# Main_Circuit_Schematic.net
KiCad netlist of a schematic drawn in Altium Designer
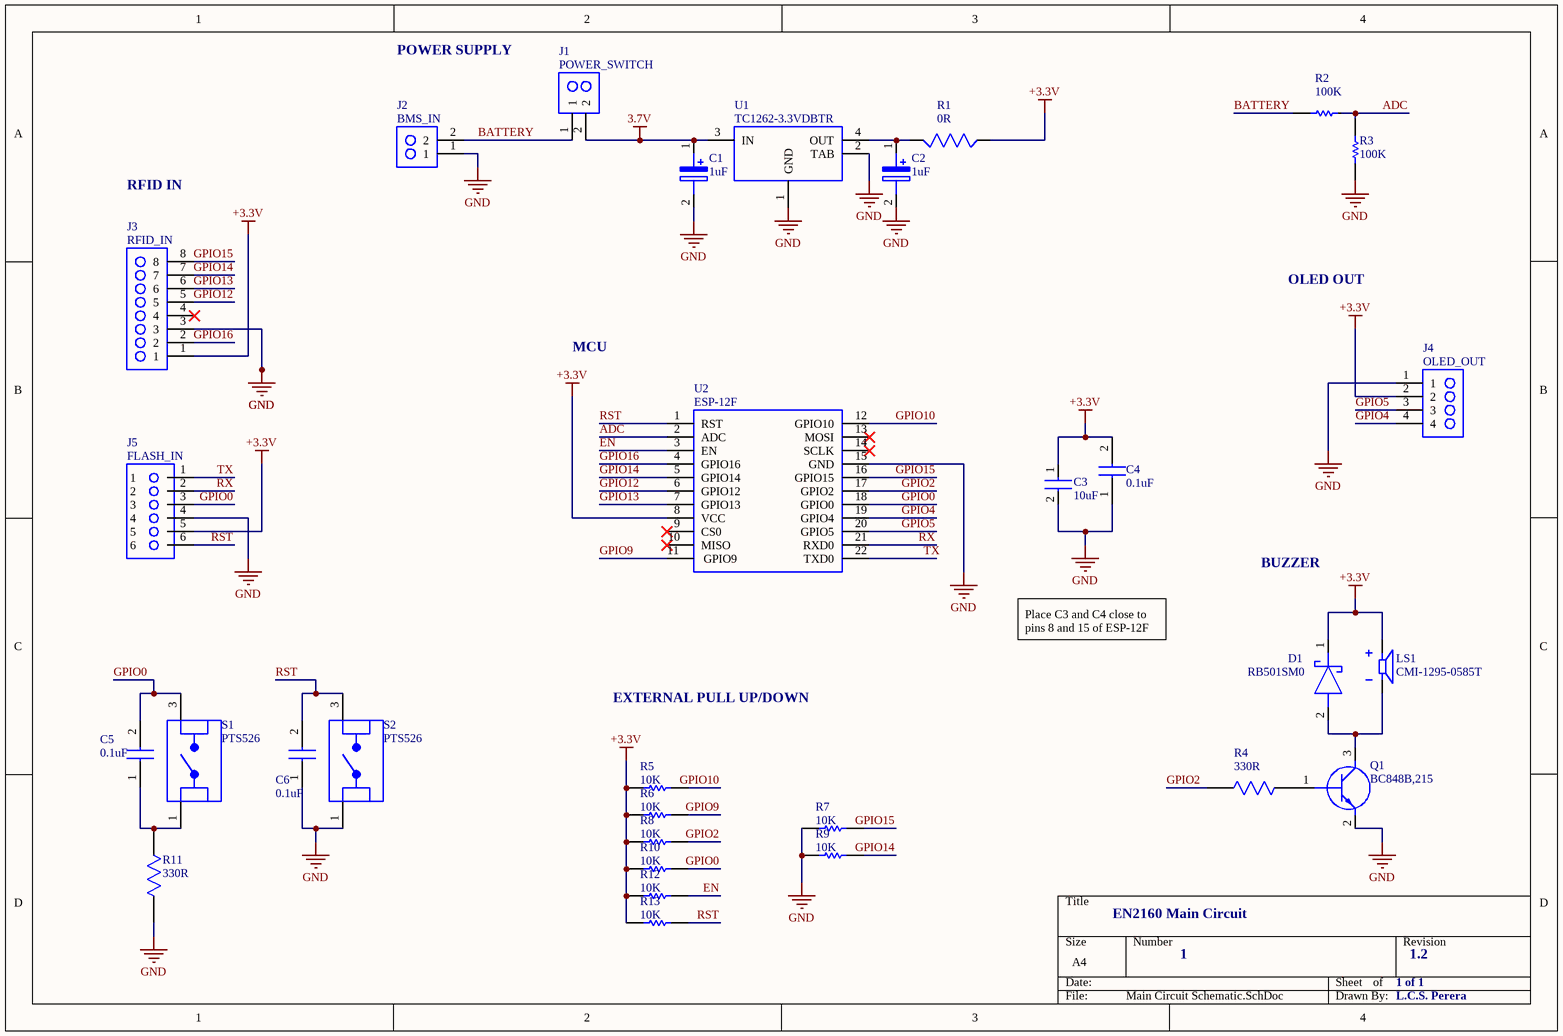
[diagram p0: Main Circuit Schematic.SchDoc]

(export (version "E")
  (design (tool "Eeschema 10.0.6"))
  (components
    (comp (ref "C1")
      (value "1uF")
      (footprint "1U")
      (description "Capacitor Polarised")
      (fields
        (field (name "MANUFACTURER_PART_NUMBER") "TAJA105K016RNJ")
        (field (name "MOUSER PART NUMBER") "581-TAJA105K016")
      )
      (libsource (lib "Schlib1") (part "TAJA105K016RNJ"))
    )
    (comp (ref "C2")
      (value "1uF")
      (footprint "1U")
      (description "Capacitor Polarised")
      (fields
        (field (name "MANUFACTURER_PART_NUMBER") "TAJA105K016RNJ")
        (field (name "MOUSER PART NUMBER") "581-TAJA105K016")
      )
      (libsource (lib "Schlib1") (part "TAJA105K016RNJ"))
    )
    (comp (ref "C3")
      (value "10uF")
      (footprint "10ucer")
      (description "10ÂµF Â±10% 10V Ceramic Capacitor X5R 0805 (2012 Metric)")
      (fields
        (field (name "MF") "Samsung Electro-Mechanics")
        (field (name "DIGI-KEY_PART_NUMBER") "1276-6456-1-ND")
      )
      (libsource (lib "Schlib1") (part "10uF"))
    )
    (comp (ref "C4")
      (value "0.1uF")
      (footprint "100n")
      (description "Capacitor")
      (fields
        (field (name "MANUFACTURER_PART_NUMBER") "C0603C104K1RACTU")
        (field (name "MOUSER PART NUMBER") "80-C0603C104K1RACTU")
      )
      (libsource (lib "Schlib1") (part "0.1uF"))
    )
    (comp (ref "C5")
      (value "0.1uF")
      (footprint "100n")
      (description "Capacitor")
      (fields
        (field (name "MANUFACTURER_PART_NUMBER") "C0603C104K1RACTU")
        (field (name "MOUSER PART NUMBER") "80-C0603C104K1RACTU")
      )
      (libsource (lib "Schlib1") (part "0.1uF"))
    )
    (comp (ref "C6")
      (value "0.1uF")
      (footprint "100n")
      (description "Capacitor")
      (fields
        (field (name "MANUFACTURER_PART_NUMBER") "C0603C104K1RACTU")
        (field (name "MOUSER PART NUMBER") "80-C0603C104K1RACTU")
      )
      (libsource (lib "Schlib1") (part "0.1uF"))
    )
    (comp (ref "D1")
      (value "RB501SM0")
      (footprint "Shottkey")
      (description "Schottky Diode")
      (fields (field (name "MANUFACTURER_PART_NUMBER") "RB501SM-30"))
      (libsource (lib "Schlib1") (part "RB501SM-30"))
    )
    (comp (ref "J1")
      (value "POWER_SWITCH")
      (footprint "2jst")
      (description "Connector")
      (fields (field (name "MANUFACTURER_PART_NUMBER") "B2B-XH-A(LF)(SN)"))
      (libsource (lib "Schlib1") (part "B2B-XHALFSN_"))
    )
    (comp (ref "J2")
      (value "BMS_IN")
      (footprint "2jst")
      (description "Connector")
      (fields (field (name "MANUFACTURER_PART_NUMBER") "B2B-XH-A(LF)(SN)"))
      (libsource (lib "") (part "B2B-XHALFSN__1"))
    )
    (comp (ref "J3")
      (value "RFID_IN")
      (footprint "8x1")
      (description "Connector")
      (fields
        (field (name "MANUFACTURER_PART_NUMBER") "61300811121")
        (field (name "MOUSER PART NUMBER") "710-61300811121")
      )
      (libsource (lib "Schlib1") (part "61300811121"))
    )
    (comp (ref "J4")
      (value "OLED_OUT")
      (footprint "4x1")
      (description "GROVE 2MM 4PIN VERT CONN 10PCS")
      (fields (field (name "MP") "110990030") (field (name "MF") "Seeed Technology"))
      (libsource (lib "Schlib1") (part "4x1"))
    )
    (comp (ref "J5")
      (value "FLASH_IN")
      (footprint "6x1")
      (description "6 Position Header Connector 0.100 (2.54mm) Through Hole Tin")
      (fields (field (name "MF") "Sullins Connector") (field (name "MP") "PPTC061LFBN-RC"))
      (libsource (lib "Schlib1") (part "PPTC061LFBN-RC"))
    )
    (comp (ref "LS1")
      (value "CMI-1295-0585T")
      (footprint "BUZZER")
      (description "12 mm, 5 Vdc, 85 dB, Through Hole, Driving Circuit, Magnetic Audio Indicator Buzzer")
      (fields (field (name "MF") "CUI Devices"))
      (libsource (lib "Schlib1") (part "CMI-1295-0585T"))
    )
    (comp (ref "Q1")
      (value "BC848B,215")
      (footprint "BC8488")
      (description "Transistor BJT NPN")
      (fields (field (name "MOUSER PART NUMBER") "771-BC848B215"))
      (libsource (lib "Schlib1") (part "BC848B,215"))
    )
    (comp (ref "R1")
      (value "0R")
      (footprint "0ohm")
      (description "0 Ohms Jumper 0.125W, 1/8W Chip Resistor 0805 (2012 Metric) Moisture Resistant Thick Film")
      (fields (field (name "MF") "Yageo") (field (name "MP") "RC0805JR-070RL"))
      (libsource (lib "Schlib1") (part "RC0805JR-070RL"))
    )
    (comp (ref "R2")
      (value "100K")
      (footprint "100k")
      (description "Resistor")
      (fields
        (field (name "MANUFACTURER_PART_NUMBER") "CR0805-FX-1002ELF")
        (field (name "MOUSER PART NUMBER") "652-CR0805FX-1002ELF")
      )
      (libsource (lib "Schlib1") (part "100k"))
    )
    (comp (ref "R3")
      (value "100K")
      (footprint "100k")
      (description "Resistor")
      (fields
        (field (name "MANUFACTURER_PART_NUMBER") "CR0805-FX-1002ELF")
        (field (name "MOUSER PART NUMBER") "652-CR0805FX-1002ELF")
      )
      (libsource (lib "Schlib1") (part "100k"))
    )
    (comp (ref "R4")
      (value "330R")
      (footprint "330r")
      (description "Resistor")
      (fields
        (field (name "MANUFACTURER_PART_NUMBER") "CR0805-FX-3300ELF")
        (field (name "MOUSER PART NUMBER") "652-CR0805FX-3300ELF")
      )
      (libsource (lib "Schlib1") (part "CR0805-FX-3300ELF"))
    )
    (comp (ref "R5")
      (value "10K")
      (footprint "10k")
      (description "Resistor")
      (fields
        (field (name "MANUFACTURER_PART_NUMBER") "CR0805-FX-1002ELF")
        (field (name "MOUSER PART NUMBER") "652-CR0805FX-1002ELF")
      )
      (libsource (lib "Schlib1") (part "10k"))
    )
    (comp (ref "R6")
      (value "10K")
      (footprint "10k")
      (description "Resistor")
      (fields
        (field (name "MANUFACTURER_PART_NUMBER") "CR0805-FX-1002ELF")
        (field (name "MOUSER PART NUMBER") "652-CR0805FX-1002ELF")
      )
      (libsource (lib "Schlib1") (part "10k"))
    )
    (comp (ref "R7")
      (value "10K")
      (footprint "10k")
      (description "Resistor")
      (fields
        (field (name "MANUFACTURER_PART_NUMBER") "CR0805-FX-1002ELF")
        (field (name "MOUSER PART NUMBER") "652-CR0805FX-1002ELF")
      )
      (libsource (lib "Schlib1") (part "10k"))
    )
    (comp (ref "R8")
      (value "10K")
      (footprint "10k")
      (description "Resistor")
      (fields
        (field (name "MANUFACTURER_PART_NUMBER") "CR0805-FX-1002ELF")
        (field (name "MOUSER PART NUMBER") "652-CR0805FX-1002ELF")
      )
      (libsource (lib "Schlib1") (part "10k"))
    )
    (comp (ref "R9")
      (value "10K")
      (footprint "10k")
      (description "Resistor")
      (fields
        (field (name "MANUFACTURER_PART_NUMBER") "CR0805-FX-1002ELF")
        (field (name "MOUSER PART NUMBER") "652-CR0805FX-1002ELF")
      )
      (libsource (lib "Schlib1") (part "10k"))
    )
    (comp (ref "R10")
      (value "10K")
      (footprint "10k")
      (description "Resistor")
      (fields
        (field (name "MANUFACTURER_PART_NUMBER") "CR0805-FX-1002ELF")
        (field (name "MOUSER PART NUMBER") "652-CR0805FX-1002ELF")
      )
      (libsource (lib "Schlib1") (part "10k"))
    )
    (comp (ref "R11")
      (value "330R")
      (footprint "330r")
      (description "Resistor")
      (fields
        (field (name "MANUFACTURER_PART_NUMBER") "CR0805-FX-3300ELF")
        (field (name "MOUSER PART NUMBER") "652-CR0805FX-3300ELF")
      )
      (libsource (lib "Schlib1") (part "CR0805-FX-3300ELF"))
    )
    (comp (ref "R12")
      (value "10K")
      (footprint "10k")
      (description "Resistor")
      (fields
        (field (name "MANUFACTURER_PART_NUMBER") "CR0805-FX-1002ELF")
        (field (name "MOUSER PART NUMBER") "652-CR0805FX-1002ELF")
      )
      (libsource (lib "Schlib1") (part "10k"))
    )
    (comp (ref "R13")
      (value "10K")
      (footprint "10k")
      (description "Resistor")
      (fields
        (field (name "MANUFACTURER_PART_NUMBER") "CR0805-FX-1002ELF")
        (field (name "MOUSER PART NUMBER") "652-CR0805FX-1002ELF")
      )
      (libsource (lib "Schlib1") (part "10k"))
    )
    (comp (ref "S1")
      (value "PTS526")
      (footprint "switch")
      (description "Switch")
      (fields
        (field (name "MANUFACTURER_PART_NUMBER") "PTS526 SK15 SMTR2 LFS")
        (field (name "MOUSER PART NUMBER") "611-PTS526SK15SMR2L")
      )
      (libsource (lib "Schlib1") (part "PTS526-SK15-SMTR2-LFS"))
    )
    (comp (ref "S2")
      (value "PTS526")
      (footprint "switch")
      (description "Switch")
      (fields
        (field (name "MANUFACTURER_PART_NUMBER") "PTS526 SK15 SMTR2 LFS")
        (field (name "MOUSER PART NUMBER") "611-PTS526SK15SMR2L")
      )
      (libsource (lib "Schlib1") (part "PTS526-SK15-SMTR2-LFS"))
    )
    (comp (ref "U1")
      (value "TC1262-3.3VDBTR")
      (footprint "3v3")
      (description "Integrated Circuit")
      (fields (field (name "MANUFACTURER_PART_NUMBER") "LM1117-3.3 MDC/NOPB"))
      (libsource (lib "Schlib1") (part "LM1117-3.3MDCNOPB"))
    )
    (comp (ref "U2")
      (value "ESP-12F")
      (footprint "SamacSys:esp12f")
      (description "Integrated Circuit")
      (fields (field (name "MANUFACTURER_PART_NUMBER") "esp-12f"))
      (libsource (lib "Schlib1") (part "ESP-12F"))
    )
  )
  (nets
    (net (code "1") (name "+3.3V") (class "Default")
      (node (ref "C3") (pin "1") (pinfunction "1_1") (pintype "passive"))
      (node (ref "C4") (pin "2") (pinfunction "2_2") (pintype "passive"))
      (node (ref "D1") (pin "1") (pinfunction "K_1") (pintype "passive"))
      (node (ref "J3") (pin "1") (pinfunction "1_1") (pintype "passive"))
      (node (ref "J4") (pin "2") (pinfunction "2_2") (pintype "passive"))
      (node (ref "J5") (pin "5") (pinfunction "5_5") (pintype "passive"))
      (node (ref "LS1") (pin "P") (pinfunction "P_P") (pintype "passive"))
      (node (ref "R1") (pin "2") (pinfunction "2_2") (pintype "passive"))
      (node (ref "R10") (pin "1") (pinfunction "1_1") (pintype "passive"))
      (node (ref "R12") (pin "1") (pinfunction "1_1") (pintype "passive"))
      (node (ref "R13") (pin "1") (pinfunction "1_1") (pintype "passive"))
      (node (ref "R5") (pin "1") (pinfunction "1_1") (pintype "passive"))
      (node (ref "R6") (pin "1") (pinfunction "1_1") (pintype "passive"))
      (node (ref "R8") (pin "1") (pinfunction "1_1") (pintype "passive"))
      (node (ref "U2") (pin "8") (pinfunction "VCC_8") (pintype "passive"))
    )
    (net (code "2") (name "/ADC") (class "Default")
      (node (ref "R2") (pin "1") (pinfunction "1_1") (pintype "passive"))
      (node (ref "R3") (pin "2") (pinfunction "2_2") (pintype "passive"))
      (node (ref "U2") (pin "2") (pinfunction "ADC_2") (pintype "passive"))
    )
    (net (code "3") (name "/BATTERY") (class "Default")
      (node (ref "J1") (pin "1") (pinfunction "1_1") (pintype "passive"))
      (node (ref "J2") (pin "2") (pinfunction "2_2") (pintype "passive"))
      (node (ref "R2") (pin "2") (pinfunction "2_2") (pintype "passive"))
    )
    (net (code "4") (name "/EN") (class "Default")
      (node (ref "R12") (pin "2") (pinfunction "2_2") (pintype "passive"))
      (node (ref "U2") (pin "3") (pinfunction "EN_3") (pintype "passive"))
    )
    (net (code "5") (name "/GPIO0") (class "Default")
      (node (ref "C5") (pin "2") (pinfunction "2_2") (pintype "passive"))
      (node (ref "J5") (pin "3") (pinfunction "3_3") (pintype "passive"))
      (node (ref "R10") (pin "2") (pinfunction "2_2") (pintype "passive"))
      (node (ref "S1") (pin "3") (pinfunction "NO_1_3") (pintype "passive"))
      (node (ref "U2") (pin "18") (pinfunction "GPIO0_18") (pintype "passive"))
    )
    (net (code "6") (name "/GPIO2") (class "Default")
      (node (ref "R4") (pin "2") (pinfunction "2_2") (pintype "passive"))
      (node (ref "R8") (pin "2") (pinfunction "2_2") (pintype "passive"))
      (node (ref "U2") (pin "17") (pinfunction "GPIO2_17") (pintype "passive"))
    )
    (net (code "7") (name "/GPIO4") (class "Default")
      (node (ref "J4") (pin "4") (pinfunction "4_4") (pintype "passive"))
      (node (ref "U2") (pin "19") (pinfunction "GPIO4_19") (pintype "passive"))
    )
    (net (code "8") (name "/GPIO5") (class "Default")
      (node (ref "J4") (pin "3") (pinfunction "3_3") (pintype "passive"))
      (node (ref "U2") (pin "20") (pinfunction "GPIO5_20") (pintype "passive"))
    )
    (net (code "9") (name "/GPIO9") (class "Default")
      (node (ref "R6") (pin "2") (pinfunction "2_2") (pintype "passive"))
      (node (ref "U2") (pin "11") (pinfunction "GPIO9_11") (pintype "passive"))
    )
    (net (code "10") (name "/GPIO10") (class "Default")
      (node (ref "R5") (pin "2") (pinfunction "2_2") (pintype "passive"))
      (node (ref "U2") (pin "12") (pinfunction "GPIO10_12") (pintype "passive"))
    )
    (net (code "11") (name "/GPIO12") (class "Default")
      (node (ref "J3") (pin "5") (pinfunction "5_5") (pintype "passive"))
      (node (ref "U2") (pin "6") (pinfunction "GPIO12_6") (pintype "passive"))
    )
    (net (code "12") (name "/GPIO13") (class "Default")
      (node (ref "J3") (pin "6") (pinfunction "6_6") (pintype "passive"))
      (node (ref "U2") (pin "7") (pinfunction "GPIO13_7") (pintype "passive"))
    )
    (net (code "13") (name "/GPIO14") (class "Default")
      (node (ref "J3") (pin "7") (pinfunction "7_7") (pintype "passive"))
      (node (ref "R9") (pin "2") (pinfunction "2_2") (pintype "passive"))
      (node (ref "U2") (pin "5") (pinfunction "GPIO14_5") (pintype "passive"))
    )
    (net (code "14") (name "/GPIO15") (class "Default")
      (node (ref "J3") (pin "8") (pinfunction "8_8") (pintype "passive"))
      (node (ref "R7") (pin "2") (pinfunction "2_2") (pintype "passive"))
      (node (ref "U2") (pin "16") (pinfunction "GPIO15_16") (pintype "passive"))
    )
    (net (code "15") (name "/GPIO16") (class "Default")
      (node (ref "J3") (pin "2") (pinfunction "2_2") (pintype "passive"))
      (node (ref "U2") (pin "4") (pinfunction "GPIO16_4") (pintype "passive"))
    )
    (net (code "16") (name "/RST") (class "Default")
      (node (ref "C6") (pin "2") (pinfunction "2_2") (pintype "passive"))
      (node (ref "J5") (pin "6") (pinfunction "6_6") (pintype "passive"))
      (node (ref "R13") (pin "2") (pinfunction "2_2") (pintype "passive"))
      (node (ref "S2") (pin "3") (pinfunction "NO_1_3") (pintype "passive"))
      (node (ref "U2") (pin "1") (pinfunction "RST_1") (pintype "passive"))
    )
    (net (code "17") (name "/RX") (class "Default")
      (node (ref "J5") (pin "2") (pinfunction "2_2") (pintype "passive"))
      (node (ref "U2") (pin "21") (pinfunction "RXD0_21") (pintype "passive"))
    )
    (net (code "18") (name "/TX") (class "Default")
      (node (ref "J5") (pin "1") (pinfunction "1_1") (pintype "passive"))
      (node (ref "U2") (pin "22") (pinfunction "TXD0_22") (pintype "passive"))
    )
    (net (code "19") (name "3.7V") (class "Default")
      (node (ref "C1") (pin "1") (pinfunction "+_1") (pintype "passive"))
      (node (ref "J1") (pin "2") (pinfunction "2_2") (pintype "passive"))
      (node (ref "U1") (pin "3") (pinfunction "IN_3") (pintype "passive"))
    )
    (net (code "20") (name "GND") (class "Default")
      (node (ref "C1") (pin "2") (pinfunction "-_2") (pintype "passive"))
      (node (ref "C2") (pin "2") (pinfunction "-_2") (pintype "passive"))
      (node (ref "C3") (pin "2") (pinfunction "2_2") (pintype "passive"))
      (node (ref "C4") (pin "1") (pinfunction "1_1") (pintype "passive"))
      (node (ref "C6") (pin "1") (pinfunction "1_1") (pintype "passive"))
      (node (ref "J2") (pin "1") (pinfunction "1_1") (pintype "passive"))
      (node (ref "J3") (pin "3") (pinfunction "3_3") (pintype "passive"))
      (node (ref "J4") (pin "1") (pinfunction "1_1") (pintype "passive"))
      (node (ref "J5") (pin "4") (pinfunction "4_4") (pintype "passive"))
      (node (ref "Q1") (pin "2") (pinfunction "E_2") (pintype "passive"))
      (node (ref "R11") (pin "2") (pinfunction "2_2") (pintype "passive"))
      (node (ref "R3") (pin "1") (pinfunction "1_1") (pintype "passive"))
      (node (ref "R7") (pin "1") (pinfunction "1_1") (pintype "passive"))
      (node (ref "R9") (pin "1") (pinfunction "1_1") (pintype "passive"))
      (node (ref "S2") (pin "1") (pinfunction "COM_1_1") (pintype "passive"))
      (node (ref "U1") (pin "1") (pinfunction "GND_1") (pintype "passive"))
      (node (ref "U1") (pin "2") (pinfunction "TAB_2") (pintype "passive"))
      (node (ref "U2") (pin "15") (pinfunction "GND_15") (pintype "passive"))
    )
    (net (code "21") (name "Net-(C2-+)") (class "Default")
      (node (ref "C2") (pin "1") (pinfunction "+_1") (pintype "passive"))
      (node (ref "R1") (pin "1") (pinfunction "1_1") (pintype "passive"))
      (node (ref "U1") (pin "4") (pinfunction "OUT_4") (pintype "passive"))
    )
    (net (code "22") (name "Net-(D1-A)") (class "Default")
      (node (ref "D1") (pin "2") (pinfunction "A_2") (pintype "passive"))
      (node (ref "LS1") (pin "N") (pinfunction "N_N") (pintype "passive"))
      (node (ref "Q1") (pin "3") (pinfunction "C_3") (pintype "passive"))
    )
    (net (code "23") (name "Net-(Q1-B)") (class "Default")
      (node (ref "Q1") (pin "1") (pinfunction "B_1") (pintype "passive"))
      (node (ref "R4") (pin "1") (pinfunction "1_1") (pintype "passive"))
    )
    (net (code "24") (name "Net-(S1-COM_1)") (class "Default")
      (node (ref "C5") (pin "1") (pinfunction "1_1") (pintype "passive"))
      (node (ref "R11") (pin "1") (pinfunction "1_1") (pintype "passive"))
      (node (ref "S1") (pin "1") (pinfunction "COM_1_1") (pintype "passive"))
    )
    (net (code "25") (name "unconnected-(J3-Pad4)") (class "Default")
      (node (ref "J3") (pin "4") (pinfunction "4_4") (pintype "passive+no_connect"))
    )
    (net (code "26") (name "unconnected-(U2-CS0-Pad9)") (class "Default")
      (node (ref "U2") (pin "9") (pinfunction "CS0_9") (pintype "passive+no_connect"))
    )
    (net (code "27") (name "unconnected-(U2-MISO-Pad10)") (class "Default")
      (node (ref "U2") (pin "10") (pinfunction "MISO_10") (pintype "passive+no_connect"))
    )
    (net (code "28") (name "unconnected-(U2-MOSI-Pad13)") (class "Default")
      (node (ref "U2") (pin "13") (pinfunction "MOSI_13") (pintype "passive+no_connect"))
    )
    (net (code "29") (name "unconnected-(U2-SCLK-Pad14)") (class "Default")
      (node (ref "U2") (pin "14") (pinfunction "SCLK_14") (pintype "passive+no_connect"))
    )
  )
)
